# relaytimer.net
KiCad netlist of a schematic drawn in Altium Designer
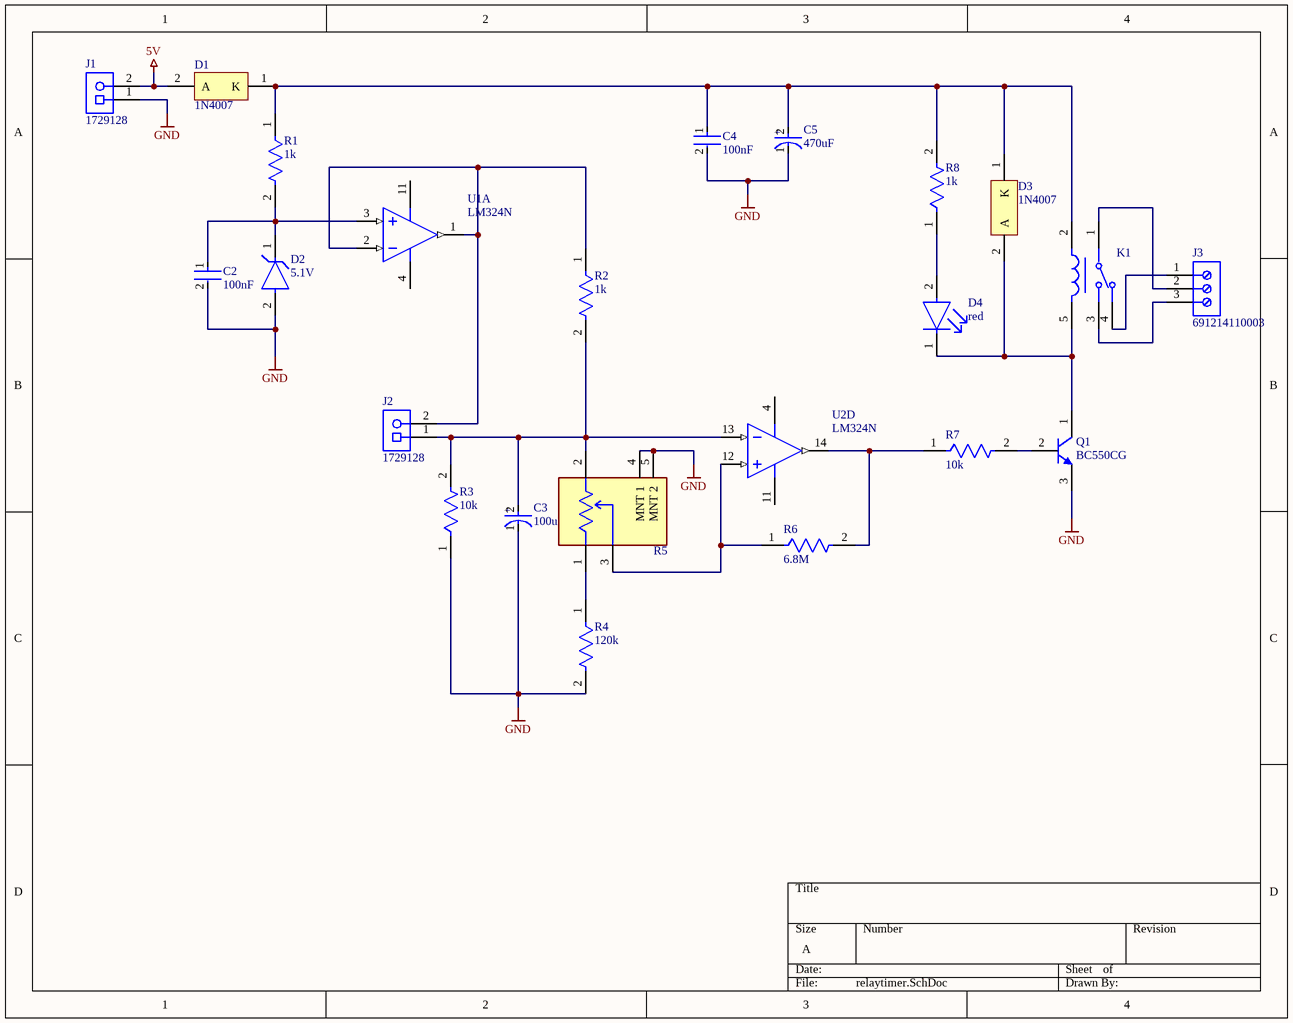
[diagram p0: relaytimer.SchDoc]

(export (version "E")
  (design (tool "Eeschema 10.0.6"))
  (components
    (comp (ref "C2")
      (value "100nF")
      (footprint "FP-RCE0K1-MFG")
      (description "Cap Ceramic 100nF 50V X7R ±10% Radial 5mm +125°C Automotive Bulk")
      (fields (field (name "VOLTAGE") "50V") (field (name "TOLERANCE") "10%"))
      (libsource (lib "Altium Content Vault") (part "b4654b650e69147ec39a6b967a45e02"))
    )
    (comp (ref "C3")
      (value "100uF")
      (footprint "FP-OS-CON-TH-C6-d_0_45-MFG")
      (description "Conductive Polymer Aluminum Solid Capacitors (OS-CON) 100uF ±20% 16V RADIAL TH 6.3x6mm")
      (fields (field (name "VOLTAGE") "16V") (field (name "TOLERANCE") "20%"))
      (libsource (lib "Altium Content Vault") (part "a00bbbee19879c290e62620ae7e47b1"))
    )
    (comp (ref "C4")
      (value "100nF")
      (footprint "FP-RCE0K1-MFG")
      (description "Cap Ceramic 100nF 50V X7R ±10% Radial 5mm +125°C Automotive Bulk")
      (fields (field (name "VOLTAGE") "50V") (field (name "TOLERANCE") "10%"))
      (libsource (lib "Altium Content Vault") (part "b4654b650e69147ec39a6b967a45e02"))
    )
    (comp (ref "C5")
      (value "470uF")
      (footprint "FP-OS-CON-TH-C6-d_0_45-MFG")
      (description "Conductive Polymer Aluminum Solid Capacitors (OS-CON) 470uF ±20% 16V RADIAL TH 6.3x6mm")
      (fields (field (name "VOLTAGE") "16V") (field (name "TOLERANCE") "20%"))
      (libsource (lib "Altium Content Vault") (part "a00bbbee19879c290e62620ae7e47b1"))
    )
    (comp (ref "D1")
      (value "1N4007")
      (footprint "ONSC-AXIAL_LEAD-2-59-10_P")
      (description "Standard Recovery Rectifier, 2-Pin Axial_Lead, Pb-Free, Bulk Bag")
      (fields (field (name "MANUFACTURER") "On Semiconductor"))
      (libsource (lib "") (part "ONSC-D-K1A2-2_A_1"))
    )
    (comp (ref "D2")
      (value "5.1V")
      (footprint "FP-017AG-MFG")
      (description "BZX79C3V3 BZX79C Series 500 mW 5.1 V 100 mA Through Hole Zener Diode - DO-35")
      (fields (field (name "TOLERANCE") "6%"))
      (libsource (lib "Altium Content Vault") (part "f813f71cba58e380607f5dd3caf9714"))
    )
    (comp (ref "D3")
      (value "1N4007")
      (footprint "ONSC-AXIAL_LEAD-2-59-10_P")
      (description "Standard Recovery Rectifier, 2-Pin Axial_Lead, Pb-Free, Bulk Bag")
      (fields (field (name "MANUFACTURER") "On Semiconductor"))
      (libsource (lib "Altium Content Vault") (part "ONSC-D-K1A2-2_A"))
    )
    (comp (ref "D4")
      (value "red")
      (footprint "FP-HLMP-1719-MFG")
      (description "LED Uni-Color Yellow 2-Pin T-1")
      (fields (field (name "MANUFACTURER") "Broadcom"))
      (libsource (lib "Altium Content Vault") (part "8706943c75ba83719d021d2fdc84c58"))
    )
    (comp (ref "J1")
      (value "1729128")
      (footprint "PHOE-1729128-2_V")
      (description "PCB Terminal Block, 13.5 A, 400 V, 2-Pin THD, RoHS, Bulk")
      (fields (field (name "MANUFACTURER") "Phoenix Contact"))
      (libsource (lib "Altium Content Vault") (part "CN-2P-F-R2"))
    )
    (comp (ref "J2")
      (value "1729128")
      (footprint "PHOE-1729128-2_V")
      (description "PCB Terminal Block, 13.5 A, 400 V, 2-Pin THD, RoHS, Bulk")
      (fields (field (name "MANUFACTURER") "Phoenix Contact"))
      (libsource (lib "Altium Content Vault") (part "CN-2P-F-R2"))
    )
    (comp (ref "J3")
      (value "691214110003")
      (footprint "691214110003")
      (fields (field (name "VOLTAGE") "300V"))
      (libsource (lib "Altium Content Vault") (part "TBL - 1R - 03P - Screw"))
    )
    (comp (ref "K1")
      (value "JS1-5V-F")
      (footprint "FP-JS1-5V-F-MFG")
      (description "RELAY GEN PURPOSE SPDT 10A 5V")
      (fields
        (field (name "OCTOPART") "https://octopart.com/js1-5v-f-panasonic-39428621")
        (field (name "MANUFACTURER") "Panasonic")
      )
      (libsource (lib "Altium Content Vault") (part "250623531296f86beaf95f2bc4a6d4c"))
    )
    (comp (ref "Q1")
      (value "BC550CG")
      (footprint "ONSC-TO-92-3-29-11")
      (description "Low Noise Transistor, NPN Silicon, 3-Pin TO-92, Pb-Free, Bulk Box")
      (fields (field (name "MANUFACTURER") "On Semiconductor"))
      (libsource (lib "Altium Content Vault") (part "ONSC-NPN-C1B2E3-3"))
    )
    (comp (ref "R1")
      (value "1k")
      (footprint "FP-MRS25-MFG")
      (fields (field (name "TOLERANCE") "1%"))
      (libsource (lib "Altium Content Vault") (part "1029c3af85768c4190bb7ad29bc67b5"))
    )
    (comp (ref "R2")
      (value "1k")
      (footprint "FP-MRS25-MFG")
      (fields (field (name "TOLERANCE") "1%"))
      (libsource (lib "Altium Content Vault") (part "1029c3af85768c4190bb7ad29bc67b5"))
    )
    (comp (ref "R3")
      (value "10k")
      (footprint "FP-MRS25-MFG")
      (fields (field (name "TOLERANCE") "1%"))
      (libsource (lib "Altium Content Vault") (part "1029c3af85768c4190bb7ad29bc67b5"))
    )
    (comp (ref "R4")
      (value "120k")
      (footprint "FP-MRS25-MFG")
      (fields (field (name "TOLERANCE") "1%"))
      (libsource (lib "Altium Content Vault") (part "1029c3af85768c4190bb7ad29bc67b5"))
    )
    (comp (ref "R5")
      (value "PTV09A-4020F-A203")
      (footprint "FP-PTV09A-4020-MFG")
      (description "POT 20K OHM 1/20W CARBON LOG")
      (fields
        (field (name "TOLERANCE") "20%")
        (field (name "OCTOPART") "https://octopart.com/ptv09a-4020f-a203-bourns-1637636")
      )
      (libsource (lib "Altium Content Vault") (part "93b1c08ba1369577c2f09b47e9e292e"))
    )
    (comp (ref "R6")
      (value "6.8M")
      (footprint "FP-MRS25-MFG")
      (fields (field (name "TOLERANCE") "1%"))
      (libsource (lib "Altium Content Vault") (part "1029c3af85768c4190bb7ad29bc67b5"))
    )
    (comp (ref "R7")
      (value "10k")
      (footprint "FP-MRS25-MFG")
      (fields (field (name "TOLERANCE") "1%"))
      (libsource (lib "Altium Content Vault") (part "1029c3af85768c4190bb7ad29bc67b5"))
    )
    (comp (ref "R8")
      (value "1k")
      (footprint "FP-MRS25-MFG")
      (fields (field (name "TOLERANCE") "1%"))
      (libsource (lib "Altium Content Vault") (part "1029c3af85768c4190bb7ad29bc67b5"))
    )
    (comp (ref "U1")
      (value "LM324N")
      (footprint "N0014A")
      (description "Low Power Quad Operational Amplifier, 14-pin MDIP")
      (fields (field (name "MANUFACTURER") "Texas Instruments"))
      (libsource (lib "Altium Content Vault") (part "AMP-OPA-LM124-14"))
    )
    (comp (ref "U2")
      (value "LM324N")
      (footprint "N0014A")
      (description "Low Power Quad Operational Amplifier, 14-pin MDIP")
      (fields (field (name "MANUFACTURER") "Texas Instruments"))
      (libsource (lib "Altium Content Vault") (part "AMP-OPA-LM124-14"))
    )
  )
  (nets
    (net (code "1") (name "5V") (class "Default")
      (node (ref "D1") (pin "2") (pinfunction "A_2") (pintype "passive"))
      (node (ref "J1") (pin "2") (pinfunction "2_2") (pintype "passive"))
    )
    (net (code "2") (name "GND") (class "Default")
      (node (ref "C2") (pin "2") (pinfunction "2_2") (pintype "passive"))
      (node (ref "C3") (pin "1") (pinfunction "C_1") (pintype "passive"))
      (node (ref "C4") (pin "2") (pinfunction "2_2") (pintype "passive"))
      (node (ref "C5") (pin "1") (pinfunction "C_1") (pintype "passive"))
      (node (ref "D2") (pin "2") (pinfunction "A_2") (pintype "passive"))
      (node (ref "J1") (pin "1") (pinfunction "1_1") (pintype "passive"))
      (node (ref "Q1") (pin "3") (pinfunction "E_3") (pintype "passive"))
      (node (ref "R3") (pin "1") (pinfunction "1_1") (pintype "passive"))
      (node (ref "R4") (pin "2") (pinfunction "2_2") (pintype "passive"))
      (node (ref "R5") (pin "4") (pinfunction "MNT_1_4") (pintype "passive"))
      (node (ref "R5") (pin "5") (pinfunction "MNT_2_5") (pintype "passive"))
    )
    (net (code "3") (name "Net-(C3-A)") (class "Default")
      (node (ref "C3") (pin "2") (pinfunction "A_2") (pintype "passive"))
      (node (ref "J2") (pin "1") (pinfunction "1_1") (pintype "passive"))
      (node (ref "R2") (pin "2") (pinfunction "2_2") (pintype "passive"))
      (node (ref "R3") (pin "2") (pinfunction "2_2") (pintype "passive"))
      (node (ref "R5") (pin "2") (pinfunction "2_2") (pintype "passive"))
      (node (ref "U2") (pin "13") (pinfunction "IN4-_13") (pintype "input"))
    )
    (net (code "4") (name "Net-(C5-A)") (class "Default")
      (node (ref "C4") (pin "1") (pinfunction "1_1") (pintype "passive"))
      (node (ref "C5") (pin "2") (pinfunction "A_2") (pintype "passive"))
      (node (ref "D1") (pin "1") (pinfunction "K_1") (pintype "passive"))
      (node (ref "D3") (pin "1") (pinfunction "K_1") (pintype "passive"))
      (node (ref "K1") (pin "2") (pinfunction "1_COIL_2") (pintype "passive"))
      (node (ref "R1") (pin "1") (pinfunction "1_1") (pintype "passive"))
      (node (ref "R8") (pin "2") (pinfunction "2_2") (pintype "passive"))
    )
    (net (code "5") (name "Net-(D2-C)") (class "Default")
      (node (ref "C2") (pin "1") (pinfunction "1_1") (pintype "passive"))
      (node (ref "D2") (pin "1") (pinfunction "C_1") (pintype "passive"))
      (node (ref "R1") (pin "2") (pinfunction "2_2") (pintype "passive"))
      (node (ref "U1") (pin "3") (pinfunction "IN1+_3") (pintype "input"))
    )
    (net (code "6") (name "Net-(D3-A)") (class "Default")
      (node (ref "D3") (pin "2") (pinfunction "A_2") (pintype "passive"))
      (node (ref "D4") (pin "1") (pinfunction "C_1") (pintype "passive"))
      (node (ref "K1") (pin "5") (pinfunction "2_COIL_5") (pintype "passive"))
      (node (ref "Q1") (pin "1") (pinfunction "C_1") (pintype "passive"))
    )
    (net (code "7") (name "Net-(D4-A)") (class "Default")
      (node (ref "D4") (pin "2") (pinfunction "A_2") (pintype "passive"))
      (node (ref "R8") (pin "1") (pinfunction "1_1") (pintype "passive"))
    )
    (net (code "8") (name "Net-(K1-COM)") (class "Default")
      (node (ref "J3") (pin "2") (pinfunction "2_2") (pintype "passive"))
      (node (ref "K1") (pin "1") (pinfunction "COM_1") (pintype "passive"))
    )
    (net (code "9") (name "Net-(K1-N.C.)") (class "Default")
      (node (ref "J3") (pin "1") (pinfunction "1_1") (pintype "passive"))
      (node (ref "K1") (pin "4") (pinfunction "N.C._4") (pintype "passive"))
    )
    (net (code "10") (name "Net-(K1-N.O.)") (class "Default")
      (node (ref "J3") (pin "3") (pinfunction "3_3") (pintype "passive"))
      (node (ref "K1") (pin "3") (pinfunction "N.O._3") (pintype "passive"))
    )
    (net (code "11") (name "Net-(Q1-B)") (class "Default")
      (node (ref "Q1") (pin "2") (pinfunction "B_2") (pintype "passive"))
      (node (ref "R7") (pin "2") (pinfunction "2_2") (pintype "passive"))
    )
    (net (code "12") (name "Net-(R4-Pad1)") (class "Default")
      (node (ref "R4") (pin "1") (pinfunction "1_1") (pintype "passive"))
      (node (ref "R5") (pin "1") (pinfunction "1_1") (pintype "passive"))
    )
    (net (code "13") (name "Net-(U1A-IN1-)") (class "Default")
      (node (ref "J2") (pin "2") (pinfunction "2_2") (pintype "passive"))
      (node (ref "R2") (pin "1") (pinfunction "1_1") (pintype "passive"))
      (node (ref "U1") (pin "1") (pinfunction "OUT1_1") (pintype "output"))
      (node (ref "U1") (pin "2") (pinfunction "IN1-_2") (pintype "input"))
    )
    (net (code "14") (name "Net-(U2D-IN4+)") (class "Default")
      (node (ref "R5") (pin "3") (pinfunction "3_3") (pintype "passive"))
      (node (ref "R6") (pin "1") (pinfunction "1_1") (pintype "passive"))
      (node (ref "U2") (pin "12") (pinfunction "IN4+_12") (pintype "input"))
    )
    (net (code "15") (name "Net-(U2D-OUT4)") (class "Default")
      (node (ref "R6") (pin "2") (pinfunction "2_2") (pintype "passive"))
      (node (ref "R7") (pin "1") (pinfunction "1_1") (pintype "passive"))
      (node (ref "U2") (pin "14") (pinfunction "OUT4_14") (pintype "output"))
    )
    (net (code "16") (name "unconnected-(U1A-GND-Pad11)") (class "Default")
      (node (ref "U1") (pin "11") (pinfunction "GND_11") (pintype "power_in"))
    )
    (net (code "17") (name "unconnected-(U1A-V+-Pad4)") (class "Default")
      (node (ref "U1") (pin "4") (pinfunction "V+_4") (pintype "power_in"))
    )
    (net (code "18") (name "unconnected-(U2D-GND-Pad11)") (class "Default")
      (node (ref "U2") (pin "11") (pinfunction "GND_11") (pintype "power_in"))
    )
    (net (code "19") (name "unconnected-(U2D-V+-Pad4)") (class "Default")
      (node (ref "U2") (pin "4") (pinfunction "V+_4") (pintype "power_in"))
    )
  )
)
